# MicrocontrollerControl.net
KiCad netlist of a schematic drawn in Altium Designer
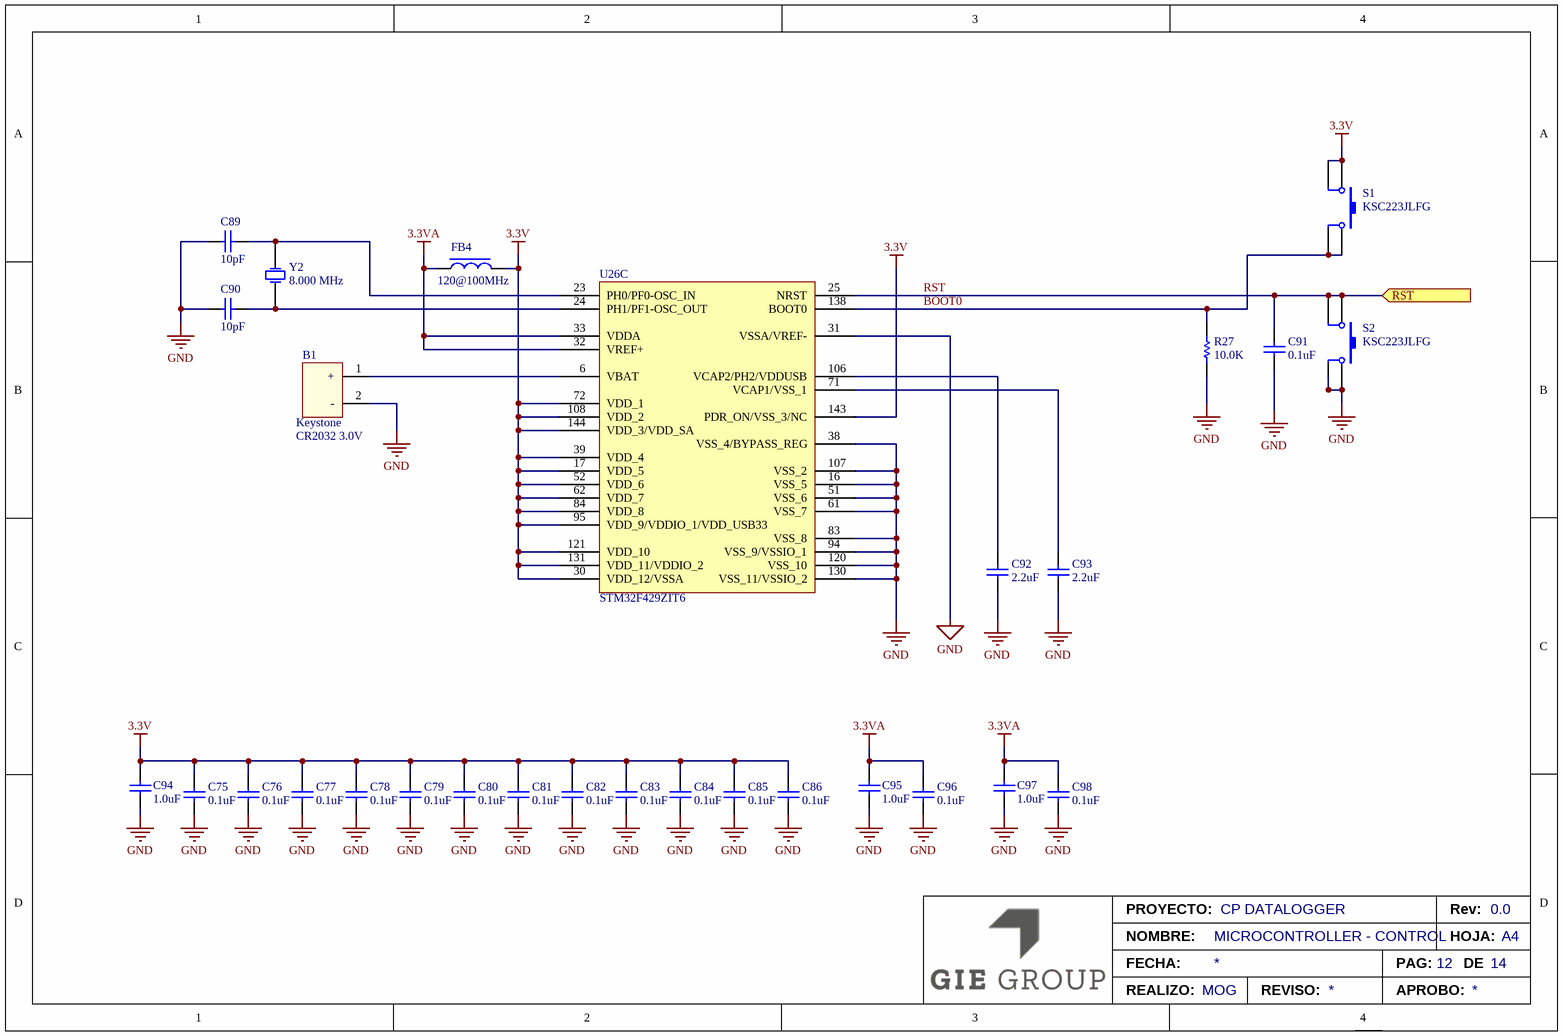
[diagram p0: MicrocontrollerControl.SchDoc]

(export (version "E")
  (design (tool "Eeschema 10.0.6"))
  (components
    (comp (ref "B1")
      (value "101")
      (footprint "Holder-CR2032-103")
      (description "HOLDER BATTERY COIN 20MM TH")
      (fields (field (name "MANUFACTURER") "Keystone") (field (name "BATERY") "CR2032 3.0V"))
      (libsource (lib "Keystone") (part "Holder 101"))
    )
    (comp (ref "C75")
      (value "0.1uF")
      (footprint "CAP-0603")
      (description "CAP CER 0.1uF 50V X7R 0603")
      (fields (field (name "PARTNUMBER") "C0603C104K5RACAUTO") (field (name "MANUFACTURER") "Kemet"))
      (libsource (lib "Kemet") (part "C0603C104K5RACAUTO"))
    )
    (comp (ref "C76")
      (value "0.1uF")
      (footprint "CAP-0603")
      (description "CAP CER 0.1uF 50V X7R 0603")
      (fields (field (name "PARTNUMBER") "C0603C104K5RACAUTO") (field (name "MANUFACTURER") "Kemet"))
      (libsource (lib "Kemet") (part "C0603C104K5RACAUTO"))
    )
    (comp (ref "C77")
      (value "0.1uF")
      (footprint "CAP-0603")
      (description "CAP CER 0.1uF 50V X7R 0603")
      (fields (field (name "PARTNUMBER") "C0603C104K5RACAUTO") (field (name "MANUFACTURER") "Kemet"))
      (libsource (lib "Kemet") (part "C0603C104K5RACAUTO"))
    )
    (comp (ref "C78")
      (value "0.1uF")
      (footprint "CAP-0603")
      (description "CAP CER 0.1uF 50V X7R 0603")
      (fields (field (name "PARTNUMBER") "C0603C104K5RACAUTO") (field (name "MANUFACTURER") "Kemet"))
      (libsource (lib "Kemet") (part "C0603C104K5RACAUTO"))
    )
    (comp (ref "C79")
      (value "0.1uF")
      (footprint "CAP-0603")
      (description "CAP CER 0.1uF 50V X7R 0603")
      (fields (field (name "PARTNUMBER") "C0603C104K5RACAUTO") (field (name "MANUFACTURER") "Kemet"))
      (libsource (lib "Kemet") (part "C0603C104K5RACAUTO"))
    )
    (comp (ref "C80")
      (value "0.1uF")
      (footprint "CAP-0603")
      (description "CAP CER 0.1uF 50V X7R 0603")
      (fields (field (name "PARTNUMBER") "C0603C104K5RACAUTO") (field (name "MANUFACTURER") "Kemet"))
      (libsource (lib "Kemet") (part "C0603C104K5RACAUTO"))
    )
    (comp (ref "C81")
      (value "0.1uF")
      (footprint "CAP-0603")
      (description "CAP CER 0.1uF 50V X7R 0603")
      (fields (field (name "PARTNUMBER") "C0603C104K5RACAUTO") (field (name "MANUFACTURER") "Kemet"))
      (libsource (lib "Kemet") (part "C0603C104K5RACAUTO"))
    )
    (comp (ref "C82")
      (value "0.1uF")
      (footprint "CAP-0603")
      (description "CAP CER 0.1uF 50V X7R 0603")
      (fields (field (name "PARTNUMBER") "C0603C104K5RACAUTO") (field (name "MANUFACTURER") "Kemet"))
      (libsource (lib "Kemet") (part "C0603C104K5RACAUTO"))
    )
    (comp (ref "C83")
      (value "0.1uF")
      (footprint "CAP-0603")
      (description "CAP CER 0.1uF 50V X7R 0603")
      (fields (field (name "PARTNUMBER") "C0603C104K5RACAUTO") (field (name "MANUFACTURER") "Kemet"))
      (libsource (lib "Kemet") (part "C0603C104K5RACAUTO"))
    )
    (comp (ref "C84")
      (value "0.1uF")
      (footprint "CAP-0603")
      (description "CAP CER 0.1uF 50V X7R 0603")
      (fields (field (name "PARTNUMBER") "C0603C104K5RACAUTO") (field (name "MANUFACTURER") "Kemet"))
      (libsource (lib "Kemet") (part "C0603C104K5RACAUTO"))
    )
    (comp (ref "C85")
      (value "0.1uF")
      (footprint "CAP-0603")
      (description "CAP CER 0.1uF 50V X7R 0603")
      (fields (field (name "PARTNUMBER") "C0603C104K5RACAUTO") (field (name "MANUFACTURER") "Kemet"))
      (libsource (lib "Kemet") (part "C0603C104K5RACAUTO"))
    )
    (comp (ref "C86")
      (value "0.1uF")
      (footprint "CAP-0603")
      (description "CAP CER 0.1uF 50V X7R 0603")
      (fields (field (name "PARTNUMBER") "C0603C104K5RACAUTO") (field (name "MANUFACTURER") "Kemet"))
      (libsource (lib "Kemet") (part "C0603C104K5RACAUTO"))
    )
    (comp (ref "C89")
      (value "10pF")
      (footprint "CAP-0603")
      (description "CAP CER 10 pF 25V C0G 0603")
      (fields (field (name "PARTNUMBER") "C0603C100K3GAC7867") (field (name "MANUFACTURER") "Kemet"))
      (libsource (lib "Kemet") (part "C0603C100K3GAC7867"))
    )
    (comp (ref "C90")
      (value "10pF")
      (footprint "CAP-0603")
      (description "CAP CER 10 pF 25V C0G 0603")
      (fields (field (name "PARTNUMBER") "C0603C100K3GAC7867") (field (name "MANUFACTURER") "Kemet"))
      (libsource (lib "Kemet") (part "C0603C100K3GAC7867"))
    )
    (comp (ref "C91")
      (value "0.1uF")
      (footprint "CAP-0603")
      (description "CAP CER 0.1uF 50V X7R 0603")
      (fields (field (name "PARTNUMBER") "C0603C104K5RACAUTO") (field (name "MANUFACTURER") "Kemet"))
      (libsource (lib "Kemet") (part "C0603C104K5RACAUTO"))
    )
    (comp (ref "C92")
      (value "2.2uF")
      (footprint "CAP-0603")
      (description "CAP CER 2.2uF 6.3V X5R 0603")
      (fields (field (name "PARTNUMBER") "C0603C225M9PAC7867") (field (name "MANUFACTURER") "Kemet"))
      (libsource (lib "Kemet") (part "C0603C225M9PAC7867"))
    )
    (comp (ref "C93")
      (value "2.2uF")
      (footprint "CAP-0603")
      (description "CAP CER 2.2uF 6.3V X5R 0603")
      (fields (field (name "PARTNUMBER") "C0603C225M9PAC7867") (field (name "MANUFACTURER") "Kemet"))
      (libsource (lib "Kemet") (part "C0603C225M9PAC7867"))
    )
    (comp (ref "C94")
      (value "1.0uF")
      (footprint "CAP-0603")
      (description "CAP CER 1uF 25V X7R 0603")
      (fields (field (name "PARTNUMBER") "C0603C105M3RAC7867") (field (name "MANUFACTURER") "Kemet"))
      (libsource (lib "Kemet") (part "C0603C105M3RAC7867"))
    )
    (comp (ref "C95")
      (value "1.0uF")
      (footprint "CAP-0603")
      (description "CAP CER 1uF 25V X7R 0603")
      (fields (field (name "PARTNUMBER") "C0603C105M3RAC7867") (field (name "MANUFACTURER") "Kemet"))
      (libsource (lib "Kemet") (part "C0603C105M3RAC7867"))
    )
    (comp (ref "C96")
      (value "0.1uF")
      (footprint "CAP-0603")
      (description "CAP CER 0.1uF 50V X7R 0603")
      (fields (field (name "PARTNUMBER") "C0603C104K5RACAUTO") (field (name "MANUFACTURER") "Kemet"))
      (libsource (lib "Kemet") (part "C0603C104K5RACAUTO"))
    )
    (comp (ref "C97")
      (value "1.0uF")
      (footprint "CAP-0603")
      (description "CAP CER 1uF 25V X7R 0603")
      (fields (field (name "PARTNUMBER") "C0603C105M3RAC7867") (field (name "MANUFACTURER") "Kemet"))
      (libsource (lib "Kemet") (part "C0603C105M3RAC7867"))
    )
    (comp (ref "C98")
      (value "0.1uF")
      (footprint "CAP-0603")
      (description "CAP CER 0.1uF 50V X7R 0603")
      (fields (field (name "PARTNUMBER") "C0603C104K5RACAUTO") (field (name "MANUFACTURER") "Kemet"))
      (libsource (lib "Kemet") (part "C0603C104K5RACAUTO"))
    )
    (comp (ref "FB4")
      (value "120@100MHz")
      (footprint "IND-0603")
      (description "Ferrite Bead 120Ohms 900mA 25% DCR=130m")
      (fields (field (name "MANUFACTURER") "Kemet") (field (name "PARTNUMBER") "Z0603C121GPWZT"))
      (libsource (lib "Kemet") (part "Z0603C121GPWZT"))
    )
    (comp (ref "R27")
      (value "10.0K")
      (footprint "RES-0603")
      (description "RES SMD 10.0K OHM 1% 1/10W 0603")
      (fields (field (name "TOLERANCE") "1%") (field (name "MANUFACTURER") "Yageo"))
      (libsource (lib "Yageo") (part "RC0603FR-0710KL"))
    )
    (comp (ref "S1")
      (value "KSC223JLFG")
      (footprint "KSC_J")
      (description "SWITCH TACTILE SPST-NO 0.01A 32V")
      (fields (field (name "MANUFACTURER") "C&K"))
      (libsource (lib "CK") (part "KSC223JLFG"))
    )
    (comp (ref "S2")
      (value "KSC223JLFG")
      (footprint "KSC_J")
      (description "SWITCH TACTILE SPST-NO 0.01A 32V")
      (fields (field (name "MANUFACTURER") "C&K"))
      (libsource (lib "CK") (part "KSC223JLFG"))
    )
    (comp (ref "U26")
      (value "STM32F429ZIT6")
      (footprint "LQFP144")
      (description "IC MCU 32BIT 2MB FLASH 144LQFP")
      (fields (field (name "MANUFACTURER") "STMicroelectronics"))
      (libsource (lib "STMicroelectronics") (part "STM32F429ZIT6"))
    )
    (comp (ref "Y2")
      (value "8.000 MHz")
      (footprint "XTAL-ABM7")
      (description "CRYSTAL 8.0000 MHZ 18PF SMD")
      (fields (field (name "PARTNUMBER") "ABM7-16.000MHZ-D-2-Y-T") (field (name "MANUFACTURER") "Abracon"))
      (libsource (lib "Abracon") (part "ABM7-8.000MHZ-D2Y-T"))
    )
  )
  (nets
    (net (code "1") (name "/BOOT0") (class "Default")
      (node (ref "R27") (pin "2") (pinfunction "2_2") (pintype "passive"))
      (node (ref "S1") (pin "2") (pinfunction "2_2") (pintype "passive"))
      (node (ref "S1") (pin "3") (pinfunction "3_3") (pintype "passive"))
      (node (ref "U26") (pin "138") (pinfunction "BOOT0_138") (pintype "passive"))
    )
    (net (code "2") (name "/RST") (class "Default")
      (node (ref "C91") (pin "2") (pinfunction "2_2") (pintype "passive"))
      (node (ref "S2") (pin "1") (pinfunction "1_1") (pintype "passive"))
      (node (ref "S2") (pin "4") (pinfunction "4_4") (pintype "passive"))
      (node (ref "U26") (pin "25") (pinfunction "NRST_25") (pintype "passive"))
    )
    (net (code "3") (name "3.3V") (class "Default")
      (node (ref "C75") (pin "2") (pinfunction "2_2") (pintype "passive"))
      (node (ref "C76") (pin "2") (pinfunction "2_2") (pintype "passive"))
      (node (ref "C77") (pin "2") (pinfunction "2_2") (pintype "passive"))
      (node (ref "C78") (pin "2") (pinfunction "2_2") (pintype "passive"))
      (node (ref "C79") (pin "2") (pinfunction "2_2") (pintype "passive"))
      (node (ref "C80") (pin "2") (pinfunction "2_2") (pintype "passive"))
      (node (ref "C81") (pin "2") (pinfunction "2_2") (pintype "passive"))
      (node (ref "C82") (pin "2") (pinfunction "2_2") (pintype "passive"))
      (node (ref "C83") (pin "2") (pinfunction "2_2") (pintype "passive"))
      (node (ref "C84") (pin "2") (pinfunction "2_2") (pintype "passive"))
      (node (ref "C85") (pin "2") (pinfunction "2_2") (pintype "passive"))
      (node (ref "C86") (pin "2") (pinfunction "2_2") (pintype "passive"))
      (node (ref "C94") (pin "2") (pinfunction "2_2") (pintype "passive"))
      (node (ref "FB4") (pin "2") (pinfunction "2_2") (pintype "passive"))
      (node (ref "S1") (pin "1") (pinfunction "1_1") (pintype "passive"))
      (node (ref "S1") (pin "4") (pinfunction "4_4") (pintype "passive"))
      (node (ref "U26") (pin "108") (pinfunction "VDD_2_108") (pintype "passive"))
      (node (ref "U26") (pin "121") (pinfunction "VDD_10_121") (pintype "passive"))
      (node (ref "U26") (pin "131") (pinfunction "VDD_11/VDDIO_2_131") (pintype "passive"))
      (node (ref "U26") (pin "143") (pinfunction "PDR_ON/VSS_3/NC_143") (pintype "passive"))
      (node (ref "U26") (pin "144") (pinfunction "VDD_3/VDD_SA_144") (pintype "passive"))
      (node (ref "U26") (pin "17") (pinfunction "VDD_5_17") (pintype "passive"))
      (node (ref "U26") (pin "30") (pinfunction "VDD_12/VSSA_30") (pintype "passive"))
      (node (ref "U26") (pin "39") (pinfunction "VDD_4_39") (pintype "passive"))
      (node (ref "U26") (pin "52") (pinfunction "VDD_6_52") (pintype "passive"))
      (node (ref "U26") (pin "62") (pinfunction "VDD_7_62") (pintype "passive"))
      (node (ref "U26") (pin "72") (pinfunction "VDD_1_72") (pintype "passive"))
      (node (ref "U26") (pin "84") (pinfunction "VDD_8_84") (pintype "passive"))
      (node (ref "U26") (pin "95") (pinfunction "VDD_9/VDDIO_1/VDD_USB33_95") (pintype "passive"))
    )
    (net (code "4") (name "3.3VA") (class "Default")
      (node (ref "C95") (pin "2") (pinfunction "2_2") (pintype "passive"))
      (node (ref "C96") (pin "2") (pinfunction "2_2") (pintype "passive"))
      (node (ref "C97") (pin "2") (pinfunction "2_2") (pintype "passive"))
      (node (ref "C98") (pin "2") (pinfunction "2_2") (pintype "passive"))
      (node (ref "FB4") (pin "1") (pinfunction "1_1") (pintype "passive"))
      (node (ref "U26") (pin "32") (pinfunction "VREF+_32") (pintype "passive"))
      (node (ref "U26") (pin "33") (pinfunction "VDDA_33") (pintype "passive"))
    )
    (net (code "5") (name "GND") (class "Default")
      (node (ref "B1") (pin "2") (pinfunction "-_2") (pintype "passive"))
      (node (ref "C75") (pin "1") (pinfunction "1_1") (pintype "passive"))
      (node (ref "C76") (pin "1") (pinfunction "1_1") (pintype "passive"))
      (node (ref "C77") (pin "1") (pinfunction "1_1") (pintype "passive"))
      (node (ref "C78") (pin "1") (pinfunction "1_1") (pintype "passive"))
      (node (ref "C79") (pin "1") (pinfunction "1_1") (pintype "passive"))
      (node (ref "C80") (pin "1") (pinfunction "1_1") (pintype "passive"))
      (node (ref "C81") (pin "1") (pinfunction "1_1") (pintype "passive"))
      (node (ref "C82") (pin "1") (pinfunction "1_1") (pintype "passive"))
      (node (ref "C83") (pin "1") (pinfunction "1_1") (pintype "passive"))
      (node (ref "C84") (pin "1") (pinfunction "1_1") (pintype "passive"))
      (node (ref "C85") (pin "1") (pinfunction "1_1") (pintype "passive"))
      (node (ref "C86") (pin "1") (pinfunction "1_1") (pintype "passive"))
      (node (ref "C89") (pin "1") (pinfunction "1_1") (pintype "passive"))
      (node (ref "C90") (pin "1") (pinfunction "1_1") (pintype "passive"))
      (node (ref "C91") (pin "1") (pinfunction "1_1") (pintype "passive"))
      (node (ref "C92") (pin "1") (pinfunction "1_1") (pintype "passive"))
      (node (ref "C93") (pin "1") (pinfunction "1_1") (pintype "passive"))
      (node (ref "C94") (pin "1") (pinfunction "1_1") (pintype "passive"))
      (node (ref "C95") (pin "1") (pinfunction "1_1") (pintype "passive"))
      (node (ref "C96") (pin "1") (pinfunction "1_1") (pintype "passive"))
      (node (ref "C97") (pin "1") (pinfunction "1_1") (pintype "passive"))
      (node (ref "C98") (pin "1") (pinfunction "1_1") (pintype "passive"))
      (node (ref "R27") (pin "1") (pinfunction "1_1") (pintype "passive"))
      (node (ref "S2") (pin "2") (pinfunction "2_2") (pintype "passive"))
      (node (ref "S2") (pin "3") (pinfunction "3_3") (pintype "passive"))
      (node (ref "U26") (pin "107") (pinfunction "VSS_2_107") (pintype "passive"))
      (node (ref "U26") (pin "120") (pinfunction "VSS_10_120") (pintype "passive"))
      (node (ref "U26") (pin "130") (pinfunction "VSS_11/VSSIO_2_130") (pintype "passive"))
      (node (ref "U26") (pin "16") (pinfunction "VSS_5_16") (pintype "passive"))
      (node (ref "U26") (pin "31") (pinfunction "VSSA/VREF-_31") (pintype "passive"))
      (node (ref "U26") (pin "38") (pinfunction "VSS_4/BYPASS_REG_38") (pintype "passive"))
      (node (ref "U26") (pin "51") (pinfunction "VSS_6_51") (pintype "passive"))
      (node (ref "U26") (pin "61") (pinfunction "VSS_7_61") (pintype "passive"))
      (node (ref "U26") (pin "83") (pinfunction "VSS_8_83") (pintype "passive"))
      (node (ref "U26") (pin "94") (pinfunction "VSS_9/VSSIO_1_94") (pintype "passive"))
    )
    (net (code "6") (name "Net-(B1-+)") (class "Default")
      (node (ref "B1") (pin "1") (pinfunction "+_1") (pintype "passive"))
      (node (ref "U26") (pin "6") (pinfunction "VBAT_6") (pintype "passive"))
    )
    (net (code "7") (name "Net-(U26C-PH0{slash}PF0-OSC_IN)") (class "Default")
      (node (ref "C89") (pin "2") (pinfunction "2_2") (pintype "passive"))
      (node (ref "U26") (pin "23") (pinfunction "PH0/PF0-OSC_IN_23") (pintype "passive"))
      (node (ref "Y2") (pin "2") (pinfunction "OSC2_2") (pintype "passive"))
    )
    (net (code "8") (name "Net-(U26C-PH1{slash}PF1-OSC_OUT)") (class "Default")
      (node (ref "C90") (pin "2") (pinfunction "2_2") (pintype "passive"))
      (node (ref "U26") (pin "24") (pinfunction "PH1/PF1-OSC_OUT_24") (pintype "passive"))
      (node (ref "Y2") (pin "1") (pinfunction "OSC1_1") (pintype "passive"))
    )
    (net (code "9") (name "Net-(U26C-VCAP1{slash}VSS_1)") (class "Default")
      (node (ref "C93") (pin "2") (pinfunction "2_2") (pintype "passive"))
      (node (ref "U26") (pin "71") (pinfunction "VCAP1/VSS_1_71") (pintype "passive"))
    )
    (net (code "10") (name "Net-(U26C-VCAP2{slash}PH2{slash}VDDUSB)") (class "Default")
      (node (ref "C92") (pin "2") (pinfunction "2_2") (pintype "passive"))
      (node (ref "U26") (pin "106") (pinfunction "VCAP2/PH2/VDDUSB_106") (pintype "passive"))
    )
  )
)
